# Microcontroller.net
KiCad netlist of a schematic drawn in Altium Designer
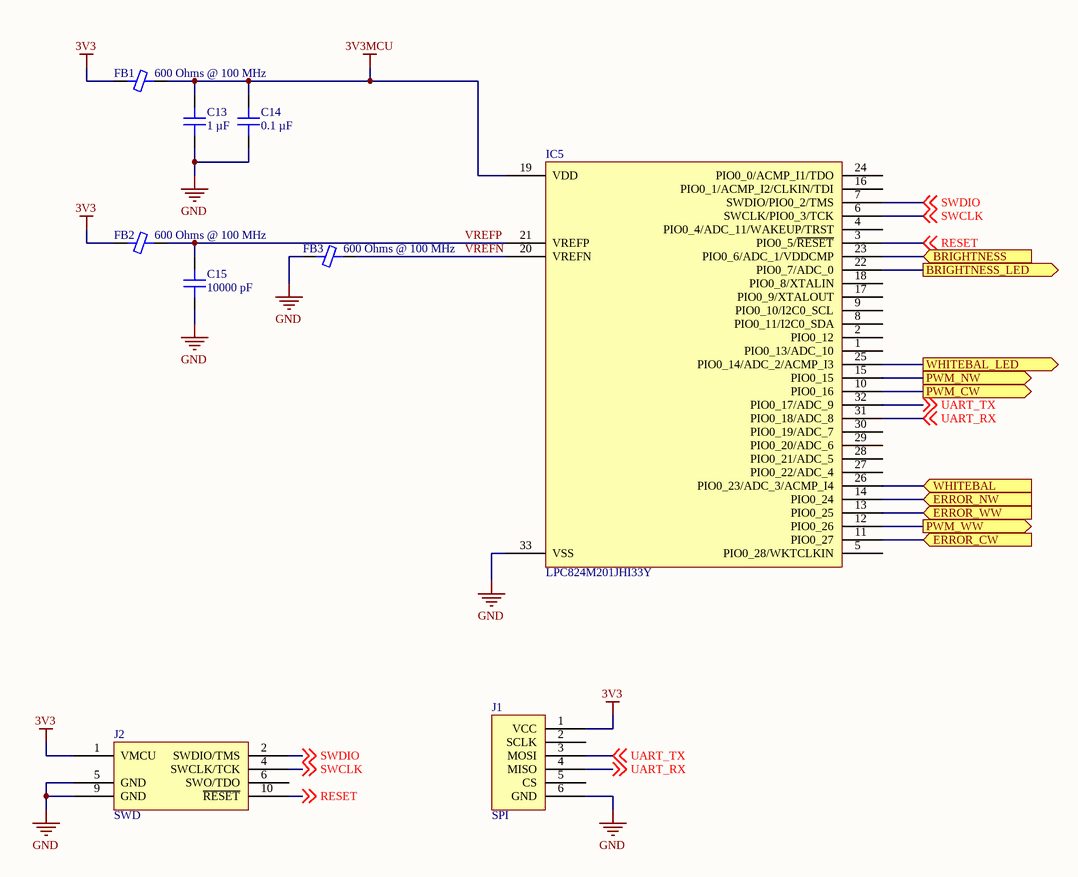
[diagram p0: Microcontroller.SchDoc]

(export (version "E")
  (design (tool "Eeschema 10.0.6"))
  (components
    (comp (ref "C13")
      (value "1 µF")
      (footprint "CAP 0603_1608")
      (description "CAP CER 1UF 10V X7R 0603")
      (fields (field (name "PART NUMBER") "CC0603KRX7R6BB105") (field (name "MANUFACTURER") "Yageo"))
      (libsource (lib "altiumlibrary.com") (part "Capacitor"))
    )
    (comp (ref "C14")
      (value "0.1 µF")
      (footprint "CAP 0603_1608")
      (description "CAP CER 0.1UF 10V X7R 0603")
      (fields (field (name "PART NUMBER") "CC0603KRX7R6BB104") (field (name "MANUFACTURER") "Yageo"))
      (libsource (lib "altiumlibrary.com") (part "Capacitor"))
    )
    (comp (ref "C15")
      (value "10000 pF")
      (footprint "CAP 0603_1608")
      (description "CAP CER 10000PF 10V X7R 0603")
      (fields (field (name "PART NUMBER") "CC0603KRX7R6BB103") (field (name "MANUFACTURER") "Yageo"))
      (libsource (lib "altiumlibrary.com") (part "Capacitor"))
    )
    (comp (ref "FB1")
      (value "600 Ohms @ 100 MHz")
      (footprint "FER 0603_1608")
      (description "MULTI-LAYER CHIP BEAD")
      (fields
        (field (name "PART NUMBER") "2506036017Y2")
        (field (name "MANUFACTURER") "Fair-Rite Products Corp.")
      )
      (libsource (lib "altiumlibrary.com") (part "Ferrite Chip"))
    )
    (comp (ref "FB2")
      (value "600 Ohms @ 100 MHz")
      (footprint "FER 0603_1608")
      (description "MULTI-LAYER CHIP BEAD")
      (fields
        (field (name "PART NUMBER") "2506036017Y2")
        (field (name "MANUFACTURER") "Fair-Rite Products Corp.")
      )
      (libsource (lib "altiumlibrary.com") (part "Ferrite Chip"))
    )
    (comp (ref "FB3")
      (value "600 Ohms @ 100 MHz")
      (footprint "FER 0603_1608")
      (description "MULTI-LAYER CHIP BEAD")
      (fields
        (field (name "PART NUMBER") "2506036017Y2")
        (field (name "MANUFACTURER") "Fair-Rite Products Corp.")
      )
      (libsource (lib "altiumlibrary.com") (part "Ferrite Chip"))
    )
    (comp (ref "IC5")
      (value "LPC824M201JHI33Y")
      (footprint "NXP HVQFN-33 5X5MM")
      (description "IC MCU 32BIT 32KB FLASH 32HVQFN")
      (fields (field (name "MANUFACTURER") "NXP USA Inc."))
      (libsource (lib "altiumlibrary.com") (part "NXP LPC82x 33Pin"))
    )
    (comp (ref "J1")
      (value "SPI")
      (footprint "SPI Breakout")
      (libsource (lib "CelestialUseful") (part "SPI"))
    )
    (comp (ref "J2") (value "SWD") (footprint "10 Pin SWD") (libsource (lib "CelestialUseful") (part "SWD")))
  )
  (nets
    (net (code "1") (name "/BRIGHTNESS") (class "Default")
      (node (ref "IC5") (pin "23") (pinfunction "PIO0_6/ADC_1/VDDCMP_23") (pintype "passive"))
    )
    (net (code "2") (name "/BRIGHTNESS_LED") (class "Default")
      (node (ref "IC5") (pin "22") (pinfunction "PIO0_7/ADC_0_22") (pintype "passive"))
    )
    (net (code "3") (name "/ERROR_CW") (class "Default")
      (node (ref "IC5") (pin "11") (pinfunction "PIO0_27_11") (pintype "passive"))
    )
    (net (code "4") (name "/ERROR_NW") (class "Default")
      (node (ref "IC5") (pin "14") (pinfunction "PIO0_24_14") (pintype "passive"))
    )
    (net (code "5") (name "/ERROR_WW") (class "Default")
      (node (ref "IC5") (pin "13") (pinfunction "PIO0_25_13") (pintype "passive"))
    )
    (net (code "6") (name "/PWM_CW") (class "Default")
      (node (ref "IC5") (pin "10") (pinfunction "PIO0_16_10") (pintype "passive"))
    )
    (net (code "7") (name "/PWM_NW") (class "Default")
      (node (ref "IC5") (pin "15") (pinfunction "PIO0_15_15") (pintype "passive"))
    )
    (net (code "8") (name "/PWM_WW") (class "Default")
      (node (ref "IC5") (pin "12") (pinfunction "PIO0_26_12") (pintype "passive"))
    )
    (net (code "9") (name "/VREFN") (class "Default")
      (node (ref "FB3") (pin "2") (pinfunction "2_2") (pintype "passive"))
      (node (ref "IC5") (pin "20") (pinfunction "VREFN_20") (pintype "passive"))
    )
    (net (code "10") (name "/VREFP") (class "Default")
      (node (ref "C15") (pin "2") (pinfunction "2_2") (pintype "passive"))
      (node (ref "FB2") (pin "2") (pinfunction "2_2") (pintype "passive"))
      (node (ref "IC5") (pin "21") (pinfunction "VREFP_21") (pintype "passive"))
    )
    (net (code "11") (name "/WHITEBAL") (class "Default")
      (node (ref "IC5") (pin "26") (pinfunction "PIO0_23/ADC_3/ACMP_I4_26") (pintype "passive"))
    )
    (net (code "12") (name "/WHITEBAL_LED") (class "Default")
      (node (ref "IC5") (pin "25") (pinfunction "PIO0_14/ADC_2/ACMP_I3_25") (pintype "passive"))
    )
    (net (code "13") (name "3V3") (class "Default")
      (node (ref "FB1") (pin "1") (pinfunction "1_1") (pintype "passive"))
      (node (ref "FB2") (pin "1") (pinfunction "1_1") (pintype "passive"))
      (node (ref "J1") (pin "1") (pinfunction "VCC_1") (pintype "passive"))
      (node (ref "J2") (pin "1") (pinfunction "VMCU_1") (pintype "passive"))
    )
    (net (code "14") (name "3V3MCU") (class "Default")
      (node (ref "C13") (pin "2") (pinfunction "2_2") (pintype "passive"))
      (node (ref "C14") (pin "2") (pinfunction "2_2") (pintype "passive"))
      (node (ref "FB1") (pin "2") (pinfunction "2_2") (pintype "passive"))
      (node (ref "IC5") (pin "19") (pinfunction "VDD_19") (pintype "passive"))
    )
    (net (code "15") (name "GND") (class "Default")
      (node (ref "C13") (pin "1") (pinfunction "1_1") (pintype "passive"))
      (node (ref "C14") (pin "1") (pinfunction "1_1") (pintype "passive"))
      (node (ref "C15") (pin "1") (pinfunction "1_1") (pintype "passive"))
      (node (ref "FB3") (pin "1") (pinfunction "1_1") (pintype "passive"))
      (node (ref "IC5") (pin "33") (pinfunction "VSS_33") (pintype "passive"))
      (node (ref "J1") (pin "6") (pinfunction "GND_6") (pintype "passive"))
      (node (ref "J2") (pin "5") (pinfunction "GND_5") (pintype "passive"))
      (node (ref "J2") (pin "9") (pinfunction "GND_9") (pintype "passive"))
    )
    (net (code "16") (name "RESET") (class "Default")
      (node (ref "IC5") (pin "3") (pinfunction "PIO0_5/~{RESET}_3") (pintype "passive"))
      (node (ref "J2") (pin "10") (pinfunction "~{RESET}_10") (pintype "passive"))
    )
    (net (code "17") (name "SWCLK") (class "Default")
      (node (ref "IC5") (pin "6") (pinfunction "SWCLK/PIO0_3/TCK_6") (pintype "passive"))
      (node (ref "J2") (pin "4") (pinfunction "SWCLK/TCK_4") (pintype "passive"))
    )
    (net (code "18") (name "SWDIO") (class "Default")
      (node (ref "IC5") (pin "7") (pinfunction "SWDIO/PIO0_2/TMS_7") (pintype "passive"))
      (node (ref "J2") (pin "2") (pinfunction "SWDIO/TMS_2") (pintype "passive"))
    )
    (net (code "19") (name "UART_RX") (class "Default")
      (node (ref "IC5") (pin "31") (pinfunction "PIO0_18/ADC_8_31") (pintype "passive"))
      (node (ref "J1") (pin "4") (pinfunction "MISO_4") (pintype "passive"))
    )
    (net (code "20") (name "UART_TX") (class "Default")
      (node (ref "IC5") (pin "32") (pinfunction "PIO0_17/ADC_9_32") (pintype "passive"))
      (node (ref "J1") (pin "3") (pinfunction "MOSI_3") (pintype "passive"))
    )
    (net (code "21") (name "unconnected-(IC5-PIO0_0{slash}ACMP_I1{slash}TDO-Pad24)") (class "Default")
      (node (ref "IC5") (pin "24") (pinfunction "PIO0_0/ACMP_I1/TDO_24") (pintype "passive"))
    )
    (net (code "22") (name "unconnected-(IC5-PIO0_1{slash}ACMP_I2{slash}CLKIN{slash}TDI-Pad16)") (class "Default")
      (node (ref "IC5") (pin "16") (pinfunction "PIO0_1/ACMP_I2/CLKIN/TDI_16") (pintype "passive"))
    )
    (net (code "23") (name "unconnected-(IC5-PIO0_4{slash}ADC_11{slash}WAKEUP{slash}TRST-Pad4)") (class "Default")
      (node (ref "IC5") (pin "4") (pinfunction "PIO0_4/ADC_11/WAKEUP/TRST_4") (pintype "passive"))
    )
    (net (code "24") (name "unconnected-(IC5-PIO0_8{slash}XTALIN-Pad18)") (class "Default")
      (node (ref "IC5") (pin "18") (pinfunction "PIO0_8/XTALIN_18") (pintype "passive"))
    )
    (net (code "25") (name "unconnected-(IC5-PIO0_9{slash}XTALOUT-Pad17)") (class "Default")
      (node (ref "IC5") (pin "17") (pinfunction "PIO0_9/XTALOUT_17") (pintype "passive"))
    )
    (net (code "26") (name "unconnected-(IC5-PIO0_10{slash}I2C0_SCL-Pad9)") (class "Default")
      (node (ref "IC5") (pin "9") (pinfunction "PIO0_10/I2C0_SCL_9") (pintype "passive"))
    )
    (net (code "27") (name "unconnected-(IC5-PIO0_11{slash}I2C0_SDA-Pad8)") (class "Default")
      (node (ref "IC5") (pin "8") (pinfunction "PIO0_11/I2C0_SDA_8") (pintype "passive"))
    )
    (net (code "28") (name "unconnected-(IC5-PIO0_12-Pad2)") (class "Default")
      (node (ref "IC5") (pin "2") (pinfunction "PIO0_12_2") (pintype "passive"))
    )
    (net (code "29") (name "unconnected-(IC5-PIO0_13{slash}ADC_10-Pad1)") (class "Default")
      (node (ref "IC5") (pin "1") (pinfunction "PIO0_13/ADC_10_1") (pintype "passive"))
    )
    (net (code "30") (name "unconnected-(IC5-PIO0_19{slash}ADC_7-Pad30)") (class "Default")
      (node (ref "IC5") (pin "30") (pinfunction "PIO0_19/ADC_7_30") (pintype "passive"))
    )
    (net (code "31") (name "unconnected-(IC5-PIO0_20{slash}ADC_6-Pad29)") (class "Default")
      (node (ref "IC5") (pin "29") (pinfunction "PIO0_20/ADC_6_29") (pintype "passive"))
    )
    (net (code "32") (name "unconnected-(IC5-PIO0_21{slash}ADC_5-Pad28)") (class "Default")
      (node (ref "IC5") (pin "28") (pinfunction "PIO0_21/ADC_5_28") (pintype "passive"))
    )
    (net (code "33") (name "unconnected-(IC5-PIO0_22{slash}ADC_4-Pad27)") (class "Default")
      (node (ref "IC5") (pin "27") (pinfunction "PIO0_22/ADC_4_27") (pintype "passive"))
    )
    (net (code "34") (name "unconnected-(IC5-PIO0_28{slash}WKTCLKIN-Pad5)") (class "Default")
      (node (ref "IC5") (pin "5") (pinfunction "PIO0_28/WKTCLKIN_5") (pintype "passive"))
    )
    (net (code "35") (name "unconnected-(J1-CS-Pad5)") (class "Default")
      (node (ref "J1") (pin "5") (pinfunction "CS_5") (pintype "passive"))
    )
    (net (code "36") (name "unconnected-(J1-SCLK-Pad2)") (class "Default")
      (node (ref "J1") (pin "2") (pinfunction "SCLK_2") (pintype "passive"))
    )
    (net (code "37") (name "unconnected-(J2-SWO{slash}TDO-Pad6)") (class "Default")
      (node (ref "J2") (pin "6") (pinfunction "SWO/TDO_6") (pintype "passive"))
    )
  )
)
